# PROC051D_LC_Filtering_Reference.net
KiCad netlist of a schematic drawn in Altium Designer
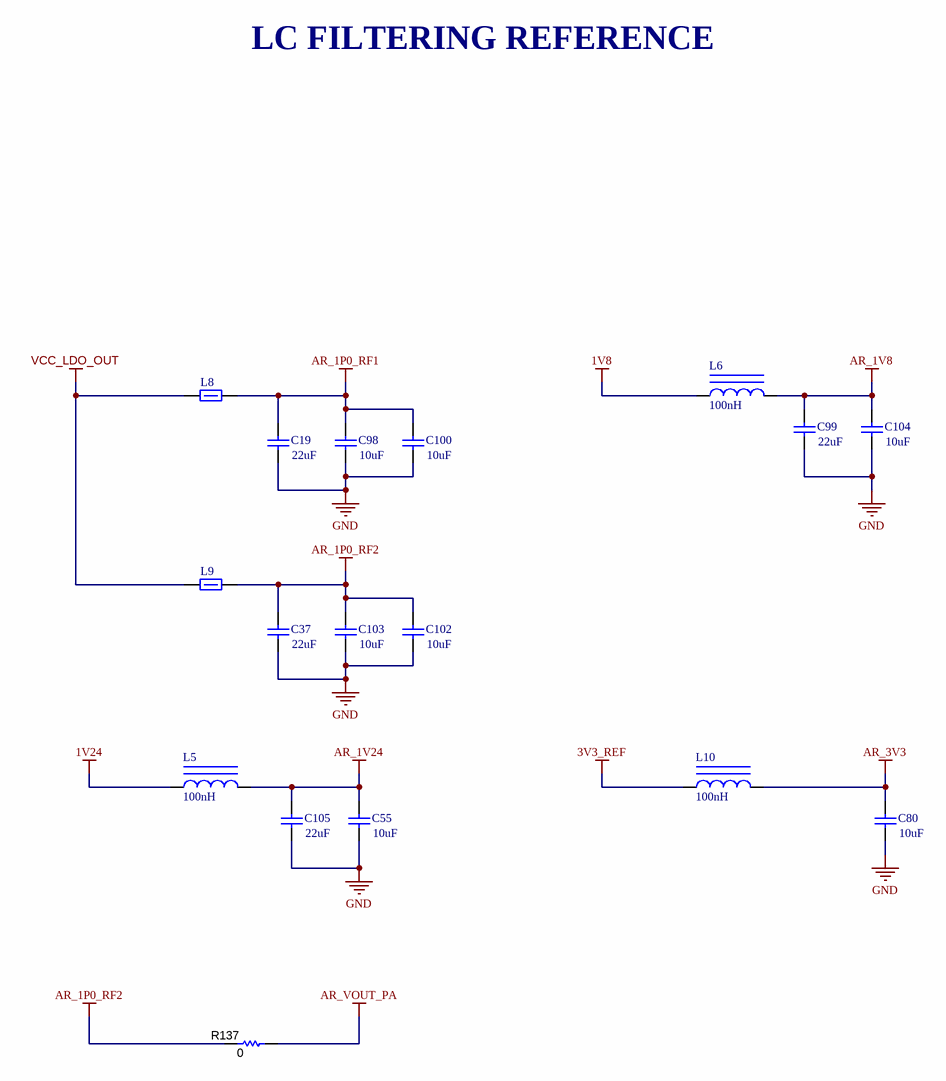
[diagram p0: PROC051D_LC_Filtering_Reference.SchDoc]

(export (version "E")
  (design (tool "Eeschema 10.0.6"))
  (components
    (comp (ref "C19")
      (value "CGA5L1X7R0J226M160AC")
      (footprint "1206_180")
      (description "CAP, CERM, 22 uF, 6.3 V, +/- 10%, X7R, AEC-Q200 Grade 1, 1206")
      (fields
        (field (name "MANUFACTURER") "TDK")
        (field (name "VALUEDISPLAYED") "22uF")
        (field (name "PUBLISHER") "Texas Instruments")
      )
      (libsource (lib "Altium Vault - TI") (part "Capacitor"))
    )
    (comp (ref "C37")
      (value "CGA5L1X7R0J226M160AC")
      (footprint "1206_180")
      (description "CAP, CERM, 22 uF, 6.3 V, +/- 10%, X7R, AEC-Q200 Grade 1, 1206")
      (fields
        (field (name "MANUFACTURER") "TDK")
        (field (name "VALUEDISPLAYED") "22uF")
        (field (name "PUBLISHER") "Texas Instruments")
      )
      (libsource (lib "Altium Vault - TI") (part "Capacitor"))
    )
    (comp (ref "C55")
      (value "GCM21BR71A106KE22L")
      (footprint "0805_HV")
      (description "CAP, CERM, 10 uF, 10 V, +/- 10%, X7R, 0805")
      (fields
        (field (name "MANUFACTURER") "MuRata")
        (field (name "VALUEDISPLAYED") "10uF")
        (field (name "PUBLISHER") "Texas Instruments")
      )
      (libsource (lib "Altium Vault - TI") (part "Capacitor"))
    )
    (comp (ref "C80")
      (value "GCM21BR71A106KE22L")
      (footprint "0805_HV")
      (description "CAP, CERM, 10 uF, 10 V, +/- 10%, X7R, 0805")
      (fields
        (field (name "MANUFACTURER") "MuRata")
        (field (name "VALUEDISPLAYED") "10uF")
        (field (name "PUBLISHER") "Texas Instruments")
      )
      (libsource (lib "Altium Vault - TI") (part "Capacitor"))
    )
    (comp (ref "C98")
      (value "GCM21BR71A106KE22L")
      (footprint "0805_HV")
      (description "CAP, CERM, 10 uF, 10 V, +/- 10%, X7R, 0805")
      (fields
        (field (name "MANUFACTURER") "MuRata")
        (field (name "VALUEDISPLAYED") "10uF")
        (field (name "PUBLISHER") "Texas Instruments")
      )
      (libsource (lib "Altium Vault - TI") (part "Capacitor"))
    )
    (comp (ref "C99")
      (value "CGA5L1X7R0J226M160AC")
      (footprint "1206_180")
      (description "CAP, CERM, 22 uF, 6.3 V, +/- 10%, X7R, AEC-Q200 Grade 1, 1206")
      (fields
        (field (name "MANUFACTURER") "TDK")
        (field (name "VALUEDISPLAYED") "22uF")
        (field (name "PUBLISHER") "Texas Instruments")
      )
      (libsource (lib "Altium Vault - TI") (part "Capacitor"))
    )
    (comp (ref "C100")
      (value "GCM21BR71A106KE22L")
      (footprint "0805_HV")
      (description "CAP, CERM, 10 uF, 10 V, +/- 10%, X7R, 0805")
      (fields
        (field (name "MANUFACTURER") "MuRata")
        (field (name "VALUEDISPLAYED") "10uF")
        (field (name "PUBLISHER") "Texas Instruments")
      )
      (libsource (lib "Altium Vault - TI") (part "Capacitor"))
    )
    (comp (ref "C102")
      (value "GCM21BR71A106KE22L")
      (footprint "0805_HV")
      (description "CAP, CERM, 10 uF, 10 V, +/- 10%, X7R, 0805")
      (fields
        (field (name "MANUFACTURER") "MuRata")
        (field (name "VALUEDISPLAYED") "10uF")
        (field (name "PUBLISHER") "Texas Instruments")
      )
      (libsource (lib "Altium Vault - TI") (part "Capacitor"))
    )
    (comp (ref "C103")
      (value "GCM21BR71A106KE22L")
      (footprint "0805_HV")
      (description "CAP, CERM, 10 uF, 10 V, +/- 10%, X7R, 0805")
      (fields
        (field (name "MANUFACTURER") "MuRata")
        (field (name "VALUEDISPLAYED") "10uF")
        (field (name "PUBLISHER") "Texas Instruments")
      )
      (libsource (lib "Altium Vault - TI") (part "Capacitor"))
    )
    (comp (ref "C104")
      (value "GCM21BR71A106KE22L")
      (footprint "0805_HV")
      (description "CAP, CERM, 10 uF, 10 V, +/- 10%, X7R, 0805")
      (fields
        (field (name "MANUFACTURER") "MuRata")
        (field (name "VALUEDISPLAYED") "10uF")
        (field (name "PUBLISHER") "Texas Instruments")
      )
      (libsource (lib "Altium Vault - TI") (part "Capacitor"))
    )
    (comp (ref "C105")
      (value "CGA5L1X7R0J226M160AC")
      (footprint "1206_180")
      (description "CAP, CERM, 22 uF, 6.3 V, +/- 10%, X7R, AEC-Q200 Grade 1, 1206")
      (fields
        (field (name "MANUFACTURER") "TDK")
        (field (name "VALUEDISPLAYED") "22uF")
        (field (name "PUBLISHER") "Texas Instruments")
      )
      (libsource (lib "Altium Vault - TI") (part "Capacitor"))
    )
    (comp (ref "L5")
      (value "NLCV32T-R10M-EFRD")
      (footprint "NLCV32")
      (description "Inductor, Wirewound, Ferrite, 100 nH, 2.85 A, 0.024 ohm, AEC-Q200 Grade 1, SMD")
      (fields (field (name "MANUFACTURER") "TDK") (field (name "VALUEDISPLAYED") "100nH"))
      (libsource (lib "Altium Vault - TI") (part "Inductor_Iron"))
    )
    (comp (ref "L6")
      (value "NLCV32T-R10M-EFRD")
      (footprint "NLCV32")
      (description "Inductor, Wirewound, Ferrite, 100 nH, 2.85 A, 0.024 ohm, AEC-Q200 Grade 1, SMD")
      (fields (field (name "MANUFACTURER") "TDK") (field (name "VALUEDISPLAYED") "100nH"))
      (libsource (lib "Altium Vault - TI") (part "Inductor_Iron"))
    )
    (comp (ref "L8")
      (value "BLM18KG121TH1D")
      (footprint "0603")
      (description "Ferrite Bead, 120 ohm @ 100 MHz, 1.9 A, 0603")
      (fields (field (name "MANUFACTURER") "MuRata"))
      (libsource (lib "Altium Vault - TI") (part "CMP-0077879-2"))
    )
    (comp (ref "L9")
      (value "BLM18KG121TH1D")
      (footprint "0603")
      (description "Ferrite Bead, 120 ohm @ 100 MHz, 1.9 A, 0603")
      (fields (field (name "MANUFACTURER") "MuRata"))
      (libsource (lib "Altium Vault - TI") (part "Ferrite_Bead"))
    )
    (comp (ref "L10")
      (value "NLCV32T-R10M-EFRD")
      (footprint "NLCV32")
      (description "Inductor, Wirewound, Ferrite, 100 nH, 2.85 A, 0.024 ohm, AEC-Q200 Grade 1, SMD")
      (fields (field (name "MANUFACTURER") "TDK") (field (name "VALUEDISPLAYED") "100nH"))
      (libsource (lib "Altium Vault - TI") (part "Inductor_Iron"))
    )
    (comp (ref "R137")
      (value "MCT06030Z0000ZP500")
      (footprint "0603")
      (description "RES, 0, 5%, 0.125 W, 0603")
      (fields
        (field (name "MANUFACTURER") "Vishay/Beyschlag")
        (field (name "VALUEDISPLAYED") "0")
        (field (name "PUBLISHER") "Texas Instruments")
      )
      (libsource (lib "Altium Vault - TI") (part "CMP-0025884-3"))
    )
  )
  (nets
    (net (code "1") (name "1V8") (class "Default")
      (node (ref "L6") (pin "1") (pinfunction "1_1") (pintype "passive"))
    )
    (net (code "2") (name "1V24") (class "Default")
      (node (ref "L5") (pin "1") (pinfunction "1_1") (pintype "passive"))
    )
    (net (code "3") (name "3V3_REF") (class "Default")
      (node (ref "L10") (pin "1") (pinfunction "1_1") (pintype "passive"))
    )
    (net (code "4") (name "AR_1P0_RF1") (class "Default")
      (node (ref "C100") (pin "1") (pinfunction "1_1") (pintype "passive"))
      (node (ref "C19") (pin "1") (pinfunction "1_1") (pintype "passive"))
      (node (ref "C98") (pin "1") (pinfunction "1_1") (pintype "passive"))
      (node (ref "L8") (pin "2") (pinfunction "2_2") (pintype "passive"))
    )
    (net (code "5") (name "AR_1P0_RF2") (class "Default")
      (node (ref "C102") (pin "1") (pinfunction "1_1") (pintype "passive"))
      (node (ref "C103") (pin "1") (pinfunction "1_1") (pintype "passive"))
      (node (ref "C37") (pin "1") (pinfunction "1_1") (pintype "passive"))
      (node (ref "L9") (pin "2") (pinfunction "2_2") (pintype "passive"))
      (node (ref "R137") (pin "1") (pinfunction "1_1") (pintype "passive"))
    )
    (net (code "6") (name "AR_1V8") (class "Default")
      (node (ref "C104") (pin "1") (pinfunction "1_1") (pintype "passive"))
      (node (ref "C99") (pin "1") (pinfunction "1_1") (pintype "passive"))
      (node (ref "L6") (pin "2") (pinfunction "2_2") (pintype "passive"))
    )
    (net (code "7") (name "AR_1V24") (class "Default")
      (node (ref "C105") (pin "1") (pinfunction "1_1") (pintype "passive"))
      (node (ref "C55") (pin "1") (pinfunction "1_1") (pintype "passive"))
      (node (ref "L5") (pin "2") (pinfunction "2_2") (pintype "passive"))
    )
    (net (code "8") (name "AR_3V3") (class "Default")
      (node (ref "C80") (pin "1") (pinfunction "1_1") (pintype "passive"))
      (node (ref "L10") (pin "2") (pinfunction "2_2") (pintype "passive"))
    )
    (net (code "9") (name "AR_VOUT_PA") (class "Default")
      (node (ref "R137") (pin "2") (pinfunction "2_2") (pintype "passive"))
    )
    (net (code "10") (name "GND") (class "Default")
      (node (ref "C100") (pin "2") (pinfunction "2_2") (pintype "passive"))
      (node (ref "C102") (pin "2") (pinfunction "2_2") (pintype "passive"))
      (node (ref "C103") (pin "2") (pinfunction "2_2") (pintype "passive"))
      (node (ref "C104") (pin "2") (pinfunction "2_2") (pintype "passive"))
      (node (ref "C105") (pin "2") (pinfunction "2_2") (pintype "passive"))
      (node (ref "C19") (pin "2") (pinfunction "2_2") (pintype "passive"))
      (node (ref "C37") (pin "2") (pinfunction "2_2") (pintype "passive"))
      (node (ref "C55") (pin "2") (pinfunction "2_2") (pintype "passive"))
      (node (ref "C80") (pin "2") (pinfunction "2_2") (pintype "passive"))
      (node (ref "C98") (pin "2") (pinfunction "2_2") (pintype "passive"))
      (node (ref "C99") (pin "2") (pinfunction "2_2") (pintype "passive"))
    )
    (net (code "11") (name "VCC_LDO_OUT") (class "Default")
      (node (ref "L8") (pin "1") (pinfunction "1_1") (pintype "passive"))
      (node (ref "L9") (pin "1") (pinfunction "1_1") (pintype "passive"))
    )
  )
)
